# slot.net
KiCad netlist of a schematic drawn in EAGLE
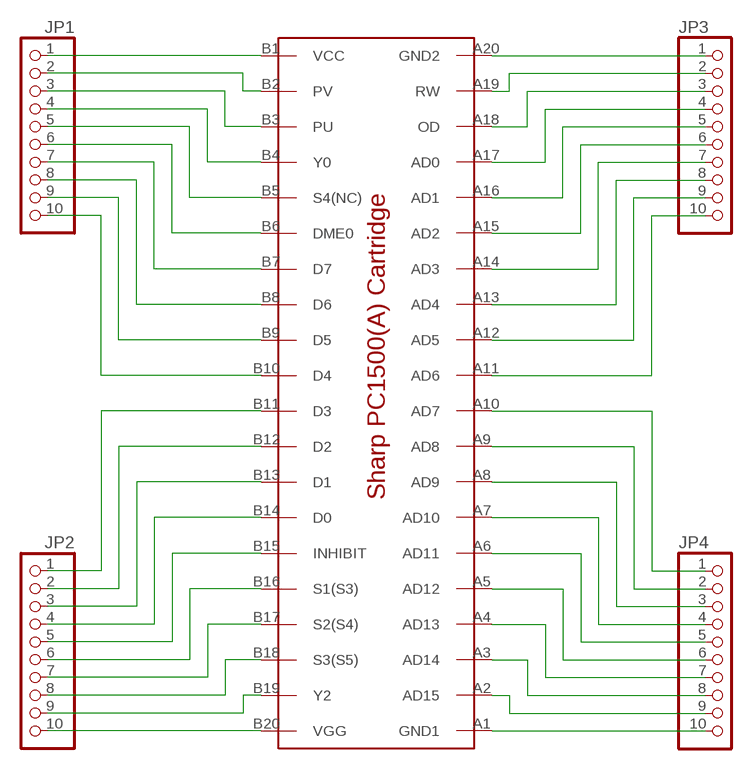
[diagram p0: schematic, sheet 1]

(export (version "E")
  (design (tool "Eeschema 10.0.6"))
  (components
    (comp (ref "JP1")
      (value "PINHD-1X10")
      (footprint "eagle-import:1X10")
      (libsource (lib "eagle-import") (part "PINHD-1X10"))
    )
    (comp (ref "JP2")
      (value "PINHD-1X10")
      (footprint "eagle-import:1X10")
      (libsource (lib "eagle-import") (part "PINHD-1X10"))
    )
    (comp (ref "JP3")
      (value "PINHD-1X10")
      (footprint "eagle-import:1X10")
      (libsource (lib "eagle-import") (part "PINHD-1X10"))
    )
    (comp (ref "JP4")
      (value "PINHD-1X10")
      (footprint "eagle-import:1X10")
      (libsource (lib "eagle-import") (part "PINHD-1X10"))
    )
    (comp (ref "U$1")
      (value "SHARP-PC1500-SLOT")
      (footprint "eagle-import:SHARP-PC1500-SLOT")
      (libsource (lib "eagle-import") (part "SHARP-PC1500-SLOT"))
    )
  )
  (nets
    (net (code "1") (name "Net-(U$1-AD0)") (class "Default")
      (node (ref "JP3") (pin "4") (pinfunction "4_4") (pintype "passive"))
      (node (ref "U$1") (pin "A17") (pinfunction "AD0_A17") (pintype "bidirectional"))
    )
    (net (code "2") (name "Net-(U$1-AD1)") (class "Default")
      (node (ref "JP3") (pin "5") (pinfunction "5_5") (pintype "passive"))
      (node (ref "U$1") (pin "A16") (pinfunction "AD1_A16") (pintype "bidirectional"))
    )
    (net (code "3") (name "Net-(U$1-AD2)") (class "Default")
      (node (ref "JP3") (pin "6") (pinfunction "6_6") (pintype "passive"))
      (node (ref "U$1") (pin "A15") (pinfunction "AD2_A15") (pintype "bidirectional"))
    )
    (net (code "4") (name "Net-(U$1-AD3)") (class "Default")
      (node (ref "JP3") (pin "7") (pinfunction "7_7") (pintype "passive"))
      (node (ref "U$1") (pin "A14") (pinfunction "AD3_A14") (pintype "bidirectional"))
    )
    (net (code "5") (name "Net-(U$1-AD4)") (class "Default")
      (node (ref "JP3") (pin "8") (pinfunction "8_8") (pintype "passive"))
      (node (ref "U$1") (pin "A13") (pinfunction "AD4_A13") (pintype "bidirectional"))
    )
    (net (code "6") (name "Net-(U$1-AD5)") (class "Default")
      (node (ref "JP3") (pin "9") (pinfunction "9_9") (pintype "passive"))
      (node (ref "U$1") (pin "A12") (pinfunction "AD5_A12") (pintype "bidirectional"))
    )
    (net (code "7") (name "Net-(U$1-AD6)") (class "Default")
      (node (ref "JP3") (pin "10") (pinfunction "10_10") (pintype "passive"))
      (node (ref "U$1") (pin "A11") (pinfunction "AD6_A11") (pintype "bidirectional"))
    )
    (net (code "8") (name "Net-(U$1-AD7)") (class "Default")
      (node (ref "JP4") (pin "1") (pinfunction "1_1") (pintype "passive"))
      (node (ref "U$1") (pin "A10") (pinfunction "AD7_A10") (pintype "bidirectional"))
    )
    (net (code "9") (name "Net-(U$1-AD8)") (class "Default")
      (node (ref "JP4") (pin "2") (pinfunction "2_2") (pintype "passive"))
      (node (ref "U$1") (pin "A9") (pinfunction "AD8_A9") (pintype "bidirectional"))
    )
    (net (code "10") (name "Net-(U$1-AD9)") (class "Default")
      (node (ref "JP4") (pin "3") (pinfunction "3_3") (pintype "passive"))
      (node (ref "U$1") (pin "A8") (pinfunction "AD9_A8") (pintype "bidirectional"))
    )
    (net (code "11") (name "Net-(U$1-AD10)") (class "Default")
      (node (ref "JP4") (pin "4") (pinfunction "4_4") (pintype "passive"))
      (node (ref "U$1") (pin "A7") (pinfunction "AD10_A7") (pintype "bidirectional"))
    )
    (net (code "12") (name "Net-(U$1-AD11)") (class "Default")
      (node (ref "JP4") (pin "5") (pinfunction "5_5") (pintype "passive"))
      (node (ref "U$1") (pin "A6") (pinfunction "AD11_A6") (pintype "bidirectional"))
    )
    (net (code "13") (name "Net-(U$1-AD12)") (class "Default")
      (node (ref "JP4") (pin "6") (pinfunction "6_6") (pintype "passive"))
      (node (ref "U$1") (pin "A5") (pinfunction "AD12_A5") (pintype "bidirectional"))
    )
    (net (code "14") (name "Net-(U$1-AD13)") (class "Default")
      (node (ref "JP4") (pin "7") (pinfunction "7_7") (pintype "passive"))
      (node (ref "U$1") (pin "A4") (pinfunction "AD13_A4") (pintype "bidirectional"))
    )
    (net (code "15") (name "Net-(U$1-AD14)") (class "Default")
      (node (ref "JP4") (pin "8") (pinfunction "8_8") (pintype "passive"))
      (node (ref "U$1") (pin "A3") (pinfunction "AD14_A3") (pintype "bidirectional"))
    )
    (net (code "16") (name "Net-(U$1-AD15)") (class "Default")
      (node (ref "JP4") (pin "9") (pinfunction "9_9") (pintype "passive"))
      (node (ref "U$1") (pin "A2") (pinfunction "AD15_A2") (pintype "bidirectional"))
    )
    (net (code "17") (name "Net-(U$1-D0)") (class "Default")
      (node (ref "JP2") (pin "4") (pinfunction "4_4") (pintype "passive"))
      (node (ref "U$1") (pin "B14") (pinfunction "D0_B14") (pintype "bidirectional"))
    )
    (net (code "18") (name "Net-(U$1-D1)") (class "Default")
      (node (ref "JP2") (pin "3") (pinfunction "3_3") (pintype "passive"))
      (node (ref "U$1") (pin "B13") (pinfunction "D1_B13") (pintype "bidirectional"))
    )
    (net (code "19") (name "Net-(U$1-D2)") (class "Default")
      (node (ref "JP2") (pin "2") (pinfunction "2_2") (pintype "passive"))
      (node (ref "U$1") (pin "B12") (pinfunction "D2_B12") (pintype "bidirectional"))
    )
    (net (code "20") (name "Net-(U$1-D3)") (class "Default")
      (node (ref "JP2") (pin "1") (pinfunction "1_1") (pintype "passive"))
      (node (ref "U$1") (pin "B11") (pinfunction "D3_B11") (pintype "bidirectional"))
    )
    (net (code "21") (name "Net-(U$1-D4)") (class "Default")
      (node (ref "JP1") (pin "10") (pinfunction "10_10") (pintype "passive"))
      (node (ref "U$1") (pin "B10") (pinfunction "D4_B10") (pintype "bidirectional"))
    )
    (net (code "22") (name "Net-(U$1-D5)") (class "Default")
      (node (ref "JP1") (pin "9") (pinfunction "9_9") (pintype "passive"))
      (node (ref "U$1") (pin "B9") (pinfunction "D5_B9") (pintype "bidirectional"))
    )
    (net (code "23") (name "Net-(U$1-D6)") (class "Default")
      (node (ref "JP1") (pin "8") (pinfunction "8_8") (pintype "passive"))
      (node (ref "U$1") (pin "B8") (pinfunction "D6_B8") (pintype "bidirectional"))
    )
    (net (code "24") (name "Net-(U$1-D7)") (class "Default")
      (node (ref "JP1") (pin "7") (pinfunction "7_7") (pintype "passive"))
      (node (ref "U$1") (pin "B7") (pinfunction "D7_B7") (pintype "bidirectional"))
    )
    (net (code "25") (name "Net-(U$1-DME0)") (class "Default")
      (node (ref "JP1") (pin "6") (pinfunction "6_6") (pintype "passive"))
      (node (ref "U$1") (pin "B6") (pinfunction "DME0_B6") (pintype "bidirectional"))
    )
    (net (code "26") (name "Net-(U$1-GND1)") (class "Default")
      (node (ref "JP4") (pin "10") (pinfunction "10_10") (pintype "passive"))
      (node (ref "U$1") (pin "A1") (pinfunction "GND1_A1") (pintype "power_in"))
    )
    (net (code "27") (name "Net-(U$1-GND2)") (class "Default")
      (node (ref "JP3") (pin "1") (pinfunction "1_1") (pintype "passive"))
      (node (ref "U$1") (pin "A20") (pinfunction "GND2_A20") (pintype "power_in"))
    )
    (net (code "28") (name "Net-(U$1-INHIBIT)") (class "Default")
      (node (ref "JP2") (pin "5") (pinfunction "5_5") (pintype "passive"))
      (node (ref "U$1") (pin "B15") (pinfunction "INHIBIT_B15") (pintype "bidirectional"))
    )
    (net (code "29") (name "Net-(U$1-OD)") (class "Default")
      (node (ref "JP3") (pin "3") (pinfunction "3_3") (pintype "passive"))
      (node (ref "U$1") (pin "A18") (pinfunction "OD_A18") (pintype "bidirectional"))
    )
    (net (code "30") (name "Net-(U$1-PU)") (class "Default")
      (node (ref "JP1") (pin "3") (pinfunction "3_3") (pintype "passive"))
      (node (ref "U$1") (pin "B3") (pinfunction "PU_B3") (pintype "bidirectional"))
    )
    (net (code "31") (name "Net-(U$1-PV)") (class "Default")
      (node (ref "JP1") (pin "2") (pinfunction "2_2") (pintype "passive"))
      (node (ref "U$1") (pin "B2") (pinfunction "PV_B2") (pintype "bidirectional"))
    )
    (net (code "32") (name "Net-(U$1-RW)") (class "Default")
      (node (ref "JP3") (pin "2") (pinfunction "2_2") (pintype "passive"))
      (node (ref "U$1") (pin "A19") (pinfunction "RW_A19") (pintype "bidirectional"))
    )
    (net (code "33") (name "Net-(U$1-S1(S3))") (class "Default")
      (node (ref "JP2") (pin "6") (pinfunction "6_6") (pintype "passive"))
      (node (ref "U$1") (pin "B16") (pinfunction "S1(S3)_B16") (pintype "bidirectional"))
    )
    (net (code "34") (name "Net-(U$1-S2(S4))") (class "Default")
      (node (ref "JP2") (pin "7") (pinfunction "7_7") (pintype "passive"))
      (node (ref "U$1") (pin "B17") (pinfunction "S2(S4)_B17") (pintype "bidirectional"))
    )
    (net (code "35") (name "Net-(U$1-S3(S5))") (class "Default")
      (node (ref "JP2") (pin "8") (pinfunction "8_8") (pintype "passive"))
      (node (ref "U$1") (pin "B18") (pinfunction "S3(S5)_B18") (pintype "bidirectional"))
    )
    (net (code "36") (name "Net-(U$1-S4(NC))") (class "Default")
      (node (ref "JP1") (pin "5") (pinfunction "5_5") (pintype "passive"))
      (node (ref "U$1") (pin "B5") (pinfunction "S4(NC)_B5") (pintype "bidirectional"))
    )
    (net (code "37") (name "Net-(U$1-VCC)") (class "Default")
      (node (ref "JP1") (pin "1") (pinfunction "1_1") (pintype "passive"))
      (node (ref "U$1") (pin "B1") (pinfunction "VCC_B1") (pintype "power_in"))
    )
    (net (code "38") (name "Net-(U$1-VGG)") (class "Default")
      (node (ref "JP2") (pin "10") (pinfunction "10_10") (pintype "passive"))
      (node (ref "U$1") (pin "B20") (pinfunction "VGG_B20") (pintype "power_in"))
    )
    (net (code "39") (name "Net-(U$1-Y0)") (class "Default")
      (node (ref "JP1") (pin "4") (pinfunction "4_4") (pintype "passive"))
      (node (ref "U$1") (pin "B4") (pinfunction "Y0_B4") (pintype "bidirectional"))
    )
    (net (code "40") (name "Net-(U$1-Y2)") (class "Default")
      (node (ref "JP2") (pin "9") (pinfunction "9_9") (pintype "passive"))
      (node (ref "U$1") (pin "B19") (pinfunction "Y2_B19") (pintype "bidirectional"))
    )
  )
)
